# KIP_2Schematic.net
KiCad netlist of a schematic drawn in Altium Designer
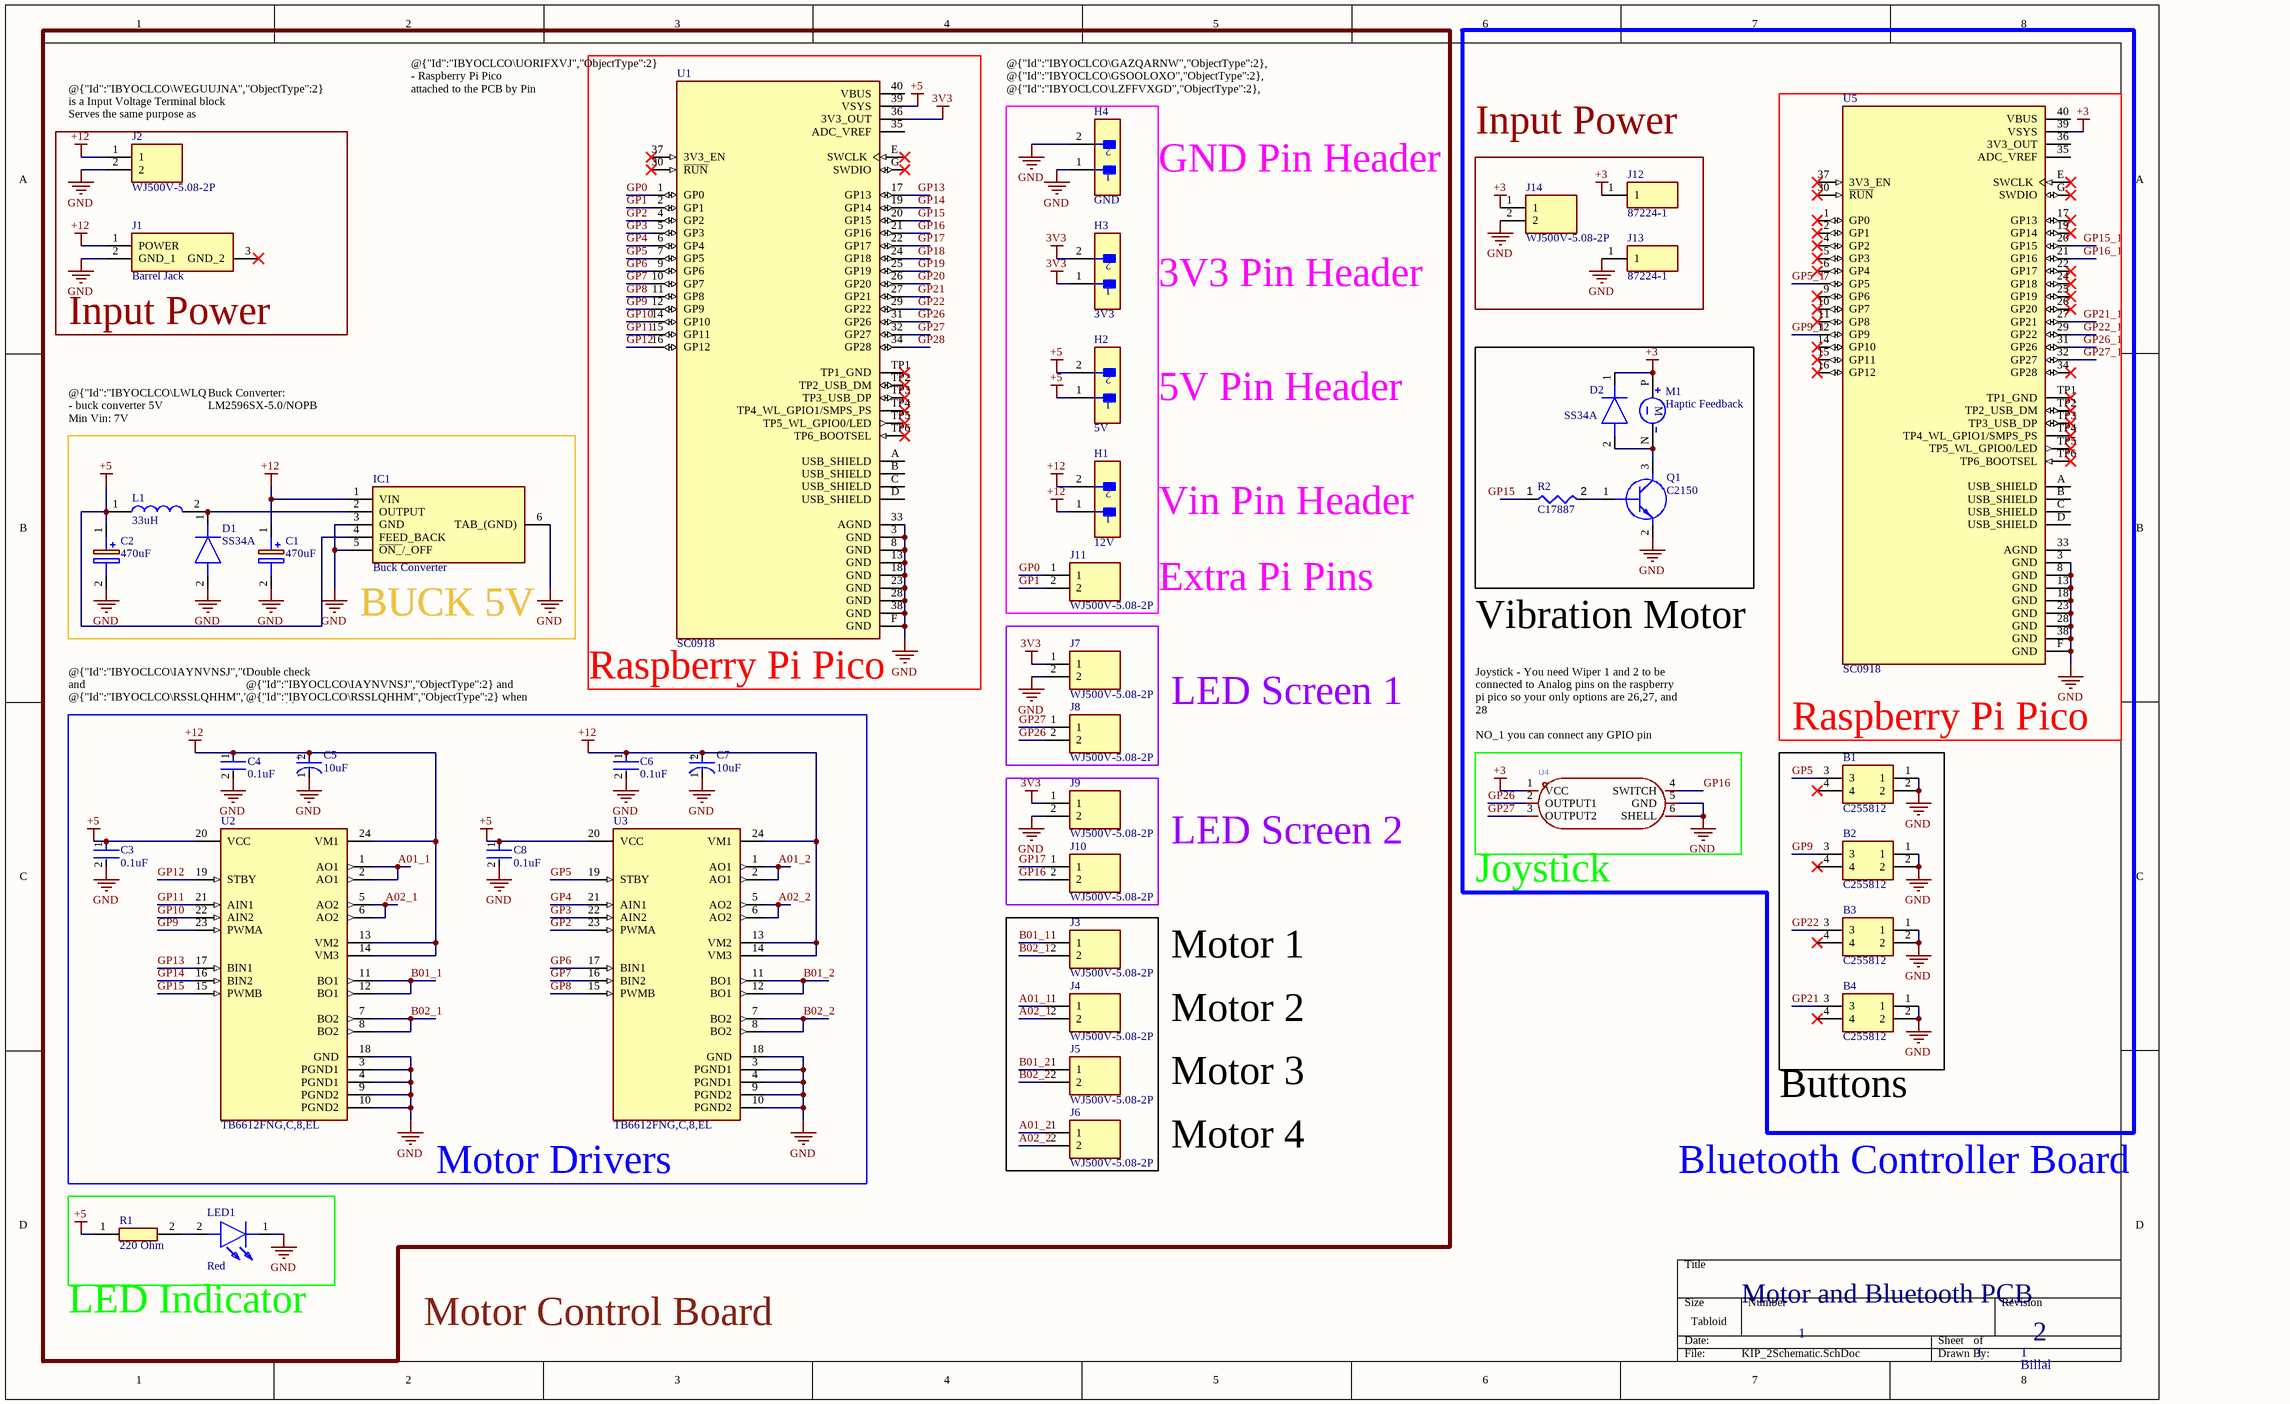
[diagram p0: KIP_2Schematic.SchDoc]

(export (version "E")
  (design (tool "Eeschema 10.0.6"))
  (components
    (comp (ref "B1")
      (value "C255812")
      (footprint "Button")
      (description "Switch")
      (fields (field (name "MANUFACTURER_PART_NUMBER") "1TS005F-2500-5001"))
      (libsource (lib "*") (part "1TS005F-2500-5001"))
    )
    (comp (ref "B2")
      (value "C255812")
      (footprint "Button")
      (description "Switch")
      (fields (field (name "MANUFACTURER_PART_NUMBER") "1TS005F-2500-5001"))
      (libsource (lib "*") (part "1TS005F-2500-5001"))
    )
    (comp (ref "B3")
      (value "C255812")
      (footprint "Button")
      (description "Switch")
      (fields (field (name "MANUFACTURER_PART_NUMBER") "1TS005F-2500-5001"))
      (libsource (lib "*") (part "1TS005F-2500-5001"))
    )
    (comp (ref "B4")
      (value "C255812")
      (footprint "Button")
      (description "Switch")
      (fields (field (name "MANUFACTURER_PART_NUMBER") "1TS005F-2500-5001"))
      (libsource (lib "*") (part "1TS005F-2500-5001"))
    )
    (comp (ref "C1")
      (value "470uF")
      (footprint "SamacSys:CAPPRD350W65D800H2200")
      (description "C178717")
      (fields
        (field (name "MANUFACTURER_PART_NUMBER") "EEU-FR1V471LB")
        (field (name "MOUSER PART NUMBER") "667-EEU-FR1V471LB")
      )
      (libsource (lib "*") (part "EEU-FR1V471LB"))
    )
    (comp (ref "C2")
      (value "470uF")
      (footprint "SamacSys:CAPPRD350W65D800H2200")
      (description "C178717")
      (fields
        (field (name "MANUFACTURER_PART_NUMBER") "EEU-FR1V471LB")
        (field (name "MOUSER PART NUMBER") "667-EEU-FR1V471LB")
      )
      (libsource (lib "*") (part "EEU-FR1V471LB"))
    )
    (comp (ref "C3")
      (value "0.1uF")
      (footprint "FP-CL779-IPC_C")
      (description "C307331")
      (libsource (lib "Altium Content Vault") (part "b4654b650e69147ec39a6b967a45e02"))
    )
    (comp (ref "C4")
      (value "0.1uF")
      (footprint "FP-CL779-IPC_C")
      (description "C307331")
      (libsource (lib "Altium Content Vault") (part "b4654b650e69147ec39a6b967a45e02"))
    )
    (comp (ref "C5")
      (value "10uF")
      (footprint "FP-TAJA-MFG")
      (description "C7171")
      (fields (field (name "VOLTAGE") "16V") (field (name "TOLERANCE") "10%"))
      (libsource (lib "Altium Content Vault") (part "203bc49f2ac43e59fd269a8c329ed05"))
    )
    (comp (ref "C6")
      (value "0.1uF")
      (footprint "FP-CL779-IPC_C")
      (description "C307331")
      (libsource (lib "Altium Content Vault") (part "b4654b650e69147ec39a6b967a45e02"))
    )
    (comp (ref "C7")
      (value "10uF")
      (footprint "FP-TAJA-MFG")
      (description "C7171")
      (fields (field (name "VOLTAGE") "16V") (field (name "TOLERANCE") "10%"))
      (libsource (lib "Altium Content Vault") (part "203bc49f2ac43e59fd269a8c329ed05"))
    )
    (comp (ref "C8")
      (value "0.1uF")
      (footprint "FP-CL779-IPC_C")
      (description "C307331")
      (libsource (lib "Altium Content Vault") (part "b4654b650e69147ec39a6b967a45e02"))
    )
    (comp (ref "D1")
      (value "SS34A")
      (footprint "SamacSys:DIOM5026X262N")
      (description "Diode")
      (libsource (lib "*") (part "SS34A"))
    )
    (comp (ref "D2")
      (value "SS34A")
      (footprint "SamacSys:DIOM5026X262N")
      (description "Diode")
      (libsource (lib "*") (part "SS34A"))
    )
    (comp (ref "H1")
      (value "12V")
      (footprint "FP-M20-9990246-MFG")
      (description "C492401")
      (fields
        (field (name "OCTOPART") "https://octopart.com/m20-9990246-harwin-2590635")
        (field (name "MANUFACTURER") "Harwin")
      )
      (libsource (lib "Altium Content Vault") (part "3bc925449376181038e59eaffc5286c"))
    )
    (comp (ref "H2")
      (value "5V")
      (footprint "FP-M20-9990246-MFG")
      (description "C492401")
      (fields
        (field (name "OCTOPART") "https://octopart.com/m20-9990246-harwin-2590635")
        (field (name "MANUFACTURER") "Harwin")
      )
      (libsource (lib "Altium Content Vault") (part "3bc925449376181038e59eaffc5286c"))
    )
    (comp (ref "H3")
      (value "3V3")
      (footprint "FP-M20-9990246-MFG")
      (description "C492401")
      (fields
        (field (name "OCTOPART") "https://octopart.com/m20-9990246-harwin-2590635")
        (field (name "MANUFACTURER") "Harwin")
      )
      (libsource (lib "Altium Content Vault") (part "3bc925449376181038e59eaffc5286c"))
    )
    (comp (ref "H4")
      (value "GND")
      (footprint "FP-M20-9990246-MFG")
      (description "C492401")
      (fields
        (field (name "OCTOPART") "https://octopart.com/m20-9990246-harwin-2590635")
        (field (name "MANUFACTURER") "Harwin")
      )
      (libsource (lib "Altium Content Vault") (part "3bc925449376181038e59eaffc5286c"))
    )
    (comp (ref "IC1")
      (value "Buck Converter")
      (footprint "SamacSys:KTT0005B")
      (description "C10002")
      (fields
        (field (name "MANUFACTURER_PART_NUMBER") "LM2596SX-5.0/NOPB")
        (field (name "MOUSER PART NUMBER") "926-LM2596SX-5.0NOPB")
      )
      (libsource (lib "*") (part "LM2596SX-5.0_NOPB"))
    )
    (comp (ref "J1")
      (value "Barrel Jack")
      (footprint "SamacSys:694106301002_1")
      (description "C5441017")
      (fields
        (field (name "MANUFACTURER_PART_NUMBER") "694106301002")
        (field (name "MOUSER PART NUMBER") "710-694106301002")
      )
      (libsource (lib "*") (part "694106301002"))
    )
    (comp (ref "J2")
      (value "WJ500V-5.08-2P")
      (footprint "SamacSys:WJ500V5082P")
      (description "C8465")
      (libsource (lib "*") (part "WJ500V-5.08-2P"))
    )
    (comp (ref "J3")
      (value "WJ500V-5.08-2P")
      (footprint "SamacSys:WJ500V5082P")
      (description "C8465")
      (libsource (lib "*") (part "WJ500V-5.08-2P"))
    )
    (comp (ref "J4")
      (value "WJ500V-5.08-2P")
      (footprint "SamacSys:WJ500V5082P")
      (description "C8465")
      (libsource (lib "*") (part "WJ500V-5.08-2P"))
    )
    (comp (ref "J5")
      (value "WJ500V-5.08-2P")
      (footprint "SamacSys:WJ500V5082P")
      (description "C8465")
      (libsource (lib "*") (part "WJ500V-5.08-2P"))
    )
    (comp (ref "J6")
      (value "WJ500V-5.08-2P")
      (footprint "SamacSys:WJ500V5082P")
      (description "C8465")
      (libsource (lib "*") (part "WJ500V-5.08-2P"))
    )
    (comp (ref "J7")
      (value "WJ500V-5.08-2P")
      (footprint "SamacSys:WJ500V5082P")
      (description "C8465")
      (libsource (lib "*") (part "WJ500V-5.08-2P"))
    )
    (comp (ref "J8")
      (value "WJ500V-5.08-2P")
      (footprint "SamacSys:WJ500V5082P")
      (description "C8465")
      (libsource (lib "*") (part "WJ500V-5.08-2P"))
    )
    (comp (ref "J9")
      (value "WJ500V-5.08-2P")
      (footprint "SamacSys:WJ500V5082P")
      (description "C8465")
      (libsource (lib "*") (part "WJ500V-5.08-2P"))
    )
    (comp (ref "J10")
      (value "WJ500V-5.08-2P")
      (footprint "SamacSys:WJ500V5082P")
      (description "C8465")
      (libsource (lib "*") (part "WJ500V-5.08-2P"))
    )
    (comp (ref "J11")
      (value "WJ500V-5.08-2P")
      (footprint "SamacSys:WJ500V5082P")
      (description "C8465")
      (libsource (lib "*") (part "WJ500V-5.08-2P"))
    )
    (comp (ref "J12")
      (value "87224-1")
      (footprint "SamacSys:HDRV1W66P0X254_1X1_213X254X1074P")
      (description "Connector")
      (fields (field (name "MOUSER PART NUMBER") "571-872241"))
      (libsource (lib "*") (part "87224-1"))
    )
    (comp (ref "J13")
      (value "87224-1")
      (footprint "SamacSys:HDRV1W66P0X254_1X1_213X254X1074P")
      (description "Connector")
      (fields (field (name "MOUSER PART NUMBER") "571-872241"))
      (libsource (lib "*") (part "87224-1"))
    )
    (comp (ref "J14")
      (value "WJ500V-5.08-2P")
      (footprint "SamacSys:WJ500V5082P")
      (description "C8465")
      (libsource (lib "*") (part "WJ500V-5.08-2P"))
    )
    (comp (ref "L1")
      (value "33uH")
      (footprint "SamacSys:INDPM144128X650N")
      (description "C364090")
      (fields (field (name "MANUFACTURER_PART_NUMBER") "SLO1365H330MTT"))
      (libsource (lib "*") (part "SLO1365H330MTT"))
    )
    (comp (ref "LED1")
      (value "Red")
      (footprint "SamacSys:LEDC1608X70N")
      (description "C2286")
      (fields (field (name "MANUFACTURER_PART_NUMBER") "KT-0603R"))
      (libsource (lib "*") (part "KT-0603R"))
    )
    (comp (ref "M1")
      (value "Haptic Feedback")
      (footprint "Haptic Feedback")
      (libsource (lib "Schlib1") (part "Haptic Feedback"))
    )
    (comp (ref "Q1")
      (value "C2150")
      (footprint "SamacSys:SOT95P240X115-3N")
      (fields
        (field (name "MANUFACTURER_PART_NUMBER") "SS8050-G")
        (field (name "MOUSER PART NUMBER") "750-SS8050-G")
      )
      (libsource (lib "*") (part "SS8050-G"))
    )
    (comp (ref "R1")
      (value "220 Ohm")
      (footprint "SamacSys:RESC2013X65N")
      (description "C17557")
      (fields
        (field (name "MANUFACTURER_PART_NUMBER") "0805W8F2200T5E")
        (field (name "MOUSER PART NUMBER") "303-0805W8F2200T5E")
      )
      (libsource (lib "*") (part "0805W8F2200T5E"))
    )
    (comp (ref "R2")
      (value "C17887")
      (footprint "Resistor 300Ohms")
      (libsource (lib "Schlib1") (part "Resistor 300Ohms"))
    )
    (comp (ref "U1")
      (value "SC0918")
      (footprint "No pin-header Pi")
      (description "Raspberry Pi Pico W RP2040")
      (fields (field (name "MANUFACTURER") "Raspberry Pi"))
      (libsource (lib "Altium Personal") (part "SC0918"))
    )
    (comp (ref "U2")
      (value "TB6612FNG,C,8,EL")
      (footprint "FP-SSOP24-P-300-0_65A-IPC_A")
      (description "C88224")
      (libsource (lib "Altium Content Vault") (part "0e8a2fe7f3780dc9c50f4d41012bdec"))
    )
    (comp (ref "U3")
      (value "TB6612FNG,C,8,EL")
      (footprint "FP-SSOP24-P-300-0_65A-IPC_A")
      (description "C88224")
      (libsource (lib "Altium Content Vault") (part "0e8a2fe7f3780dc9c50f4d41012bdec"))
    )
    (comp (ref "U4")
      (value "C42411044")
      (footprint "Correct Joystick")
      (fields
        (field (name "MANUFACTURER") "YTL(亚特联)")
        (field (name "MANUFACTURER PART") "YHE-YG16-001 SH1B166A1")
      )
      (libsource (lib "altium-import") (part "root_0_YHE-YG16-001 SH1B166A1_"))
    )
    (comp (ref "U5")
      (value "SC0918")
      (footprint "No pin-header Pi")
      (description "Raspberry Pi Pico W RP2040")
      (fields (field (name "MANUFACTURER") "Raspberry Pi"))
      (libsource (lib "Altium Personal") (part "SC0918"))
    )
  )
  (nets
    (net (code "1") (name "+3") (class "Default")
      (node (ref "D2") (pin "1") (pinfunction "K_1") (pintype "passive"))
      (node (ref "J12") (pin "1") (pinfunction "1_1") (pintype "passive"))
      (node (ref "J14") (pin "1") (pinfunction "1_1") (pintype "passive"))
      (node (ref "M1") (pin "P") (pinfunction "POS_P") (pintype "passive"))
      (node (ref "U4") (pin "1") (pinfunction "VCC_1") (pintype "passive"))
      (node (ref "U5") (pin "39") (pinfunction "VSYS_39") (pintype "power_in"))
    )
    (net (code "2") (name "+5") (class "Default")
      (node (ref "C2") (pin "1") (pinfunction "+_1") (pintype "passive"))
      (node (ref "C3") (pin "1") (pinfunction "1_1") (pintype "passive"))
      (node (ref "C8") (pin "1") (pinfunction "1_1") (pintype "passive"))
      (node (ref "H2") (pin "1") (pinfunction "1_1") (pintype "passive"))
      (node (ref "H2") (pin "2") (pinfunction "2_2") (pintype "passive"))
      (node (ref "IC1") (pin "4") (pinfunction "FEED_BACK_4") (pintype "passive"))
      (node (ref "L1") (pin "1") (pinfunction "1_1") (pintype "passive"))
      (node (ref "R1") (pin "1") (pinfunction "1_1") (pintype "passive"))
      (node (ref "U1") (pin "39") (pinfunction "VSYS_39") (pintype "power_in"))
      (node (ref "U2") (pin "20") (pinfunction "VCC_20") (pintype "power_in"))
      (node (ref "U3") (pin "20") (pinfunction "VCC_20") (pintype "power_in"))
    )
    (net (code "3") (name "+12") (class "Default")
      (node (ref "C1") (pin "1") (pinfunction "+_1") (pintype "passive"))
      (node (ref "C4") (pin "1") (pinfunction "1_1") (pintype "passive"))
      (node (ref "C5") (pin "2") (pinfunction "A_2") (pintype "passive"))
      (node (ref "C6") (pin "1") (pinfunction "1_1") (pintype "passive"))
      (node (ref "C7") (pin "2") (pinfunction "A_2") (pintype "passive"))
      (node (ref "H1") (pin "1") (pinfunction "1_1") (pintype "passive"))
      (node (ref "H1") (pin "2") (pinfunction "2_2") (pintype "passive"))
      (node (ref "IC1") (pin "1") (pinfunction "VIN_1") (pintype "passive"))
      (node (ref "J1") (pin "1") (pinfunction "POWER_1") (pintype "passive"))
      (node (ref "J2") (pin "1") (pinfunction "1_1") (pintype "passive"))
      (node (ref "U2") (pin "13") (pinfunction "VM2_13") (pintype "power_in"))
      (node (ref "U2") (pin "14") (pinfunction "VM3_14") (pintype "power_in"))
      (node (ref "U2") (pin "24") (pinfunction "VM1_24") (pintype "power_in"))
      (node (ref "U3") (pin "13") (pinfunction "VM2_13") (pintype "power_in"))
      (node (ref "U3") (pin "14") (pinfunction "VM3_14") (pintype "power_in"))
      (node (ref "U3") (pin "24") (pinfunction "VM1_24") (pintype "power_in"))
    )
    (net (code "4") (name "/A01_1") (class "Default")
      (node (ref "J4") (pin "1") (pinfunction "1_1") (pintype "passive"))
      (node (ref "U2") (pin "1") (pinfunction "AO1_1") (pintype "output"))
      (node (ref "U2") (pin "2") (pinfunction "AO1_2") (pintype "output"))
    )
    (net (code "5") (name "/A01_2") (class "Default")
      (node (ref "J6") (pin "1") (pinfunction "1_1") (pintype "passive"))
      (node (ref "U3") (pin "1") (pinfunction "AO1_1") (pintype "output"))
      (node (ref "U3") (pin "2") (pinfunction "AO1_2") (pintype "output"))
    )
    (net (code "6") (name "/A02_1") (class "Default")
      (node (ref "J4") (pin "2") (pinfunction "2_2") (pintype "passive"))
      (node (ref "U2") (pin "5") (pinfunction "AO2_5") (pintype "output"))
      (node (ref "U2") (pin "6") (pinfunction "AO2_6") (pintype "output"))
    )
    (net (code "7") (name "/A02_2") (class "Default")
      (node (ref "J6") (pin "2") (pinfunction "2_2") (pintype "passive"))
      (node (ref "U3") (pin "5") (pinfunction "AO2_5") (pintype "output"))
      (node (ref "U3") (pin "6") (pinfunction "AO2_6") (pintype "output"))
    )
    (net (code "8") (name "/B01_1") (class "Default")
      (node (ref "J3") (pin "1") (pinfunction "1_1") (pintype "passive"))
      (node (ref "U2") (pin "11") (pinfunction "BO1_11") (pintype "output"))
      (node (ref "U2") (pin "12") (pinfunction "BO1_12") (pintype "output"))
    )
    (net (code "9") (name "/B01_2") (class "Default")
      (node (ref "J5") (pin "1") (pinfunction "1_1") (pintype "passive"))
      (node (ref "U3") (pin "11") (pinfunction "BO1_11") (pintype "output"))
      (node (ref "U3") (pin "12") (pinfunction "BO1_12") (pintype "output"))
    )
    (net (code "10") (name "/B02_1") (class "Default")
      (node (ref "J3") (pin "2") (pinfunction "2_2") (pintype "passive"))
      (node (ref "U2") (pin "7") (pinfunction "BO2_7") (pintype "output"))
      (node (ref "U2") (pin "8") (pinfunction "BO2_8") (pintype "output"))
    )
    (net (code "11") (name "/B02_2") (class "Default")
      (node (ref "J5") (pin "2") (pinfunction "2_2") (pintype "passive"))
      (node (ref "U3") (pin "7") (pinfunction "BO2_7") (pintype "output"))
      (node (ref "U3") (pin "8") (pinfunction "BO2_8") (pintype "output"))
    )
    (net (code "12") (name "/GP0") (class "Default")
      (node (ref "J11") (pin "1") (pinfunction "1_1") (pintype "passive"))
      (node (ref "U1") (pin "1") (pinfunction "GP0_1") (pintype "bidirectional"))
    )
    (net (code "13") (name "/GP1") (class "Default")
      (node (ref "J11") (pin "2") (pinfunction "2_2") (pintype "passive"))
      (node (ref "U1") (pin "2") (pinfunction "GP1_2") (pintype "bidirectional"))
    )
    (net (code "14") (name "/GP2") (class "Default")
      (node (ref "U1") (pin "4") (pinfunction "GP2_4") (pintype "bidirectional"))
      (node (ref "U3") (pin "23") (pinfunction "PWMA_23") (pintype "input"))
    )
    (net (code "15") (name "/GP3") (class "Default")
      (node (ref "U1") (pin "5") (pinfunction "GP3_5") (pintype "bidirectional"))
      (node (ref "U3") (pin "22") (pinfunction "AIN2_22") (pintype "input"))
    )
    (net (code "16") (name "/GP4") (class "Default")
      (node (ref "U1") (pin "6") (pinfunction "GP4_6") (pintype "bidirectional"))
      (node (ref "U3") (pin "21") (pinfunction "AIN1_21") (pintype "input"))
    )
    (net (code "17") (name "/GP5") (class "Default")
      (node (ref "B1") (pin "3") (pinfunction "3_3") (pintype "passive"))
      (node (ref "U1") (pin "7") (pinfunction "GP5_7") (pintype "bidirectional"))
      (node (ref "U3") (pin "19") (pinfunction "STBY_19") (pintype "input"))
    )
    (net (code "18") (name "/GP5_1") (class "Default")
      (node (ref "U5") (pin "7") (pinfunction "GP5_7") (pintype "bidirectional"))
    )
    (net (code "19") (name "/GP6") (class "Default")
      (node (ref "U1") (pin "9") (pinfunction "GP6_9") (pintype "bidirectional"))
      (node (ref "U3") (pin "17") (pinfunction "BIN1_17") (pintype "input"))
    )
    (net (code "20") (name "/GP7") (class "Default")
      (node (ref "U1") (pin "10") (pinfunction "GP7_10") (pintype "bidirectional"))
      (node (ref "U3") (pin "16") (pinfunction "BIN2_16") (pintype "input"))
    )
    (net (code "21") (name "/GP8") (class "Default")
      (node (ref "U1") (pin "11") (pinfunction "GP8_11") (pintype "bidirectional"))
      (node (ref "U3") (pin "15") (pinfunction "PWMB_15") (pintype "input"))
    )
    (net (code "22") (name "/GP9") (class "Default")
      (node (ref "B2") (pin "3") (pinfunction "3_3") (pintype "passive"))
      (node (ref "U1") (pin "12") (pinfunction "GP9_12") (pintype "bidirectional"))
      (node (ref "U2") (pin "23") (pinfunction "PWMA_23") (pintype "input"))
    )
    (net (code "23") (name "/GP9_1") (class "Default")
      (node (ref "U5") (pin "12") (pinfunction "GP9_12") (pintype "bidirectional"))
    )
    (net (code "24") (name "/GP10") (class "Default")
      (node (ref "U1") (pin "14") (pinfunction "GP10_14") (pintype "bidirectional"))
      (node (ref "U2") (pin "22") (pinfunction "AIN2_22") (pintype "input"))
    )
    (net (code "25") (name "/GP11") (class "Default")
      (node (ref "U1") (pin "15") (pinfunction "GP11_15") (pintype "bidirectional"))
      (node (ref "U2") (pin "21") (pinfunction "AIN1_21") (pintype "input"))
    )
    (net (code "26") (name "/GP12") (class "Default")
      (node (ref "U1") (pin "16") (pinfunction "GP12_16") (pintype "bidirectional"))
      (node (ref "U2") (pin "19") (pinfunction "STBY_19") (pintype "input"))
    )
    (net (code "27") (name "/GP13") (class "Default")
      (node (ref "U1") (pin "17") (pinfunction "GP13_17") (pintype "bidirectional"))
      (node (ref "U2") (pin "17") (pinfunction "BIN1_17") (pintype "input"))
    )
    (net (code "28") (name "/GP14") (class "Default")
      (node (ref "U1") (pin "19") (pinfunction "GP14_19") (pintype "bidirectional"))
      (node (ref "U2") (pin "16") (pinfunction "BIN2_16") (pintype "input"))
    )
    (net (code "29") (name "/GP15") (class "Default")
      (node (ref "U1") (pin "20") (pinfunction "GP15_20") (pintype "bidirectional"))
      (node (ref "U2") (pin "15") (pinfunction "PWMB_15") (pintype "input"))
    )
    (net (code "30") (name "/GP15_1") (class "Default")
      (node (ref "U5") (pin "20") (pinfunction "GP15_20") (pintype "bidirectional"))
    )
    (net (code "31") (name "/GP16") (class "Default")
      (node (ref "J10") (pin "2") (pinfunction "2_2") (pintype "passive"))
      (node (ref "U1") (pin "21") (pinfunction "GP16_21") (pintype "bidirectional"))
      (node (ref "U4") (pin "4") (pinfunction "SWITCH_4") (pintype "passive"))
    )
    (net (code "32") (name "/GP16_1") (class "Default")
      (node (ref "U5") (pin "21") (pinfunction "GP16_21") (pintype "bidirectional"))
    )
    (net (code "33") (name "/GP17") (class "Default")
      (node (ref "J10") (pin "1") (pinfunction "1_1") (pintype "passive"))
      (node (ref "U1") (pin "22") (pinfunction "GP17_22") (pintype "bidirectional"))
    )
    (net (code "34") (name "/GP18") (class "Default")
      (node (ref "U1") (pin "24") (pinfunction "GP18_24") (pintype "bidirectional"))
    )
    (net (code "35") (name "/GP19") (class "Default")
      (node (ref "U1") (pin "25") (pinfunction "GP19_25") (pintype "bidirectional"))
    )
    (net (code "36") (name "/GP20") (class "Default")
      (node (ref "U1") (pin "26") (pinfunction "GP20_26") (pintype "bidirectional"))
    )
    (net (code "37") (name "/GP21") (class "Default")
      (node (ref "B4") (pin "3") (pinfunction "3_3") (pintype "passive"))
      (node (ref "U1") (pin "27") (pinfunction "GP21_27") (pintype "bidirectional"))
    )
    (net (code "38") (name "/GP21_1") (class "Default")
      (node (ref "U5") (pin "27") (pinfunction "GP21_27") (pintype "bidirectional"))
    )
    (net (code "39") (name "/GP22") (class "Default")
      (node (ref "B3") (pin "3") (pinfunction "3_3") (pintype "passive"))
      (node (ref "U1") (pin "29") (pinfunction "GP22_29") (pintype "bidirectional"))
    )
    (net (code "40") (name "/GP22_1") (class "Default")
      (node (ref "U5") (pin "29") (pinfunction "GP22_29") (pintype "bidirectional"))
    )
    (net (code "41") (name "/GP26") (class "Default")
      (node (ref "J8") (pin "2") (pinfunction "2_2") (pintype "passive"))
      (node (ref "U1") (pin "31") (pinfunction "GP26_31") (pintype "bidirectional"))
      (node (ref "U4") (pin "2") (pinfunction "OUTPUT1_2") (pintype "passive"))
    )
    (net (code "42") (name "/GP26_1") (class "Default")
      (node (ref "U5") (pin "31") (pinfunction "GP26_31") (pintype "bidirectional"))
    )
    (net (code "43") (name "/GP27") (class "Default")
      (node (ref "J8") (pin "1") (pinfunction "1_1") (pintype "passive"))
      (node (ref "U1") (pin "32") (pinfunction "GP27_32") (pintype "bidirectional"))
      (node (ref "U4") (pin "3") (pinfunction "OUTPUT2_3") (pintype "passive"))
    )
    (net (code "44") (name "/GP27_1") (class "Default")
      (node (ref "U5") (pin "32") (pinfunction "GP27_32") (pintype "bidirectional"))
    )
    (net (code "45") (name "/GP28") (class "Default")
      (node (ref "U1") (pin "34") (pinfunction "GP28_34") (pintype "bidirectional"))
    )
    (net (code "46") (name "3V3") (class "Default")
      (node (ref "H3") (pin "1") (pinfunction "1_1") (pintype "passive"))
      (node (ref "H3") (pin "2") (pinfunction "2_2") (pintype "passive"))
      (node (ref "J7") (pin "1") (pinfunction "1_1") (pintype "passive"))
      (node (ref "J9") (pin "1") (pinfunction "1_1") (pintype "passive"))
      (node (ref "U1") (pin "36") (pinfunction "3V3_OUT_36") (pintype "power_in"))
    )
    (net (code "47") (name "GND") (class "Default")
      (node (ref "B1") (pin "1") (pinfunction "1_1") (pintype "passive"))
      (node (ref "B1") (pin "2") (pinfunction "2_2") (pintype "passive"))
      (node (ref "B2") (pin "1") (pinfunction "1_1") (pintype "passive"))
      (node (ref "B2") (pin "2") (pinfunction "2_2") (pintype "passive"))
      (node (ref "B3") (pin "1") (pinfunction "1_1") (pintype "passive"))
      (node (ref "B3") (pin "2") (pinfunction "2_2") (pintype "passive"))
      (node (ref "B4") (pin "1") (pinfunction "1_1") (pintype "passive"))
      (node (ref "B4") (pin "2") (pinfunction "2_2") (pintype "passive"))
      (node (ref "C1") (pin "2") (pinfunction "-_2") (pintype "passive"))
      (node (ref "C2") (pin "2") (pinfunction "-_2") (pintype "passive"))
      (node (ref "C3") (pin "2") (pinfunction "2_2") (pintype "passive"))
      (node (ref "C4") (pin "2") (pinfunction "2_2") (pintype "passive"))
      (node (ref "C5") (pin "1") (pinfunction "C_1") (pintype "passive"))
      (node (ref "C6") (pin "2") (pinfunction "2_2") (pintype "passive"))
      (node (ref "C7") (pin "1") (pinfunction "C_1") (pintype "passive"))
      (node (ref "C8") (pin "2") (pinfunction "2_2") (pintype "passive"))
      (node (ref "D1") (pin "2") (pinfunction "A_2") (pintype "passive"))
      (node (ref "H4") (pin "1") (pinfunction "1_1") (pintype "passive"))
      (node (ref "H4") (pin "2") (pinfunction "2_2") (pintype "passive"))
      (node (ref "IC1") (pin "3") (pinfunction "GND_3") (pintype "passive"))
      (node (ref "IC1") (pin "5") (pinfunction "~{ON_}/_OFF_5") (pintype "passive"))
      (node (ref "IC1") (pin "6") (pinfunction "TAB_(GND)_6") (pintype "passive"))
      (node (ref "J1") (pin "2") (pinfunction "GND_1_2") (pintype "passive"))
      (node (ref "J13") (pin "1") (pinfunction "1_1") (pintype "passive"))
      (node (ref "J14") (pin "2") (pinfunction "2_2") (pintype "passive"))
      (node (ref "J2") (pin "2") (pinfunction "2_2") (pintype "passive"))
      (node (ref "J7") (pin "2") (pinfunction "2_2") (pintype "passive"))
      (node (ref "J9") (pin "2") (pinfunction "2_2") (pintype "passive"))
      (node (ref "LED1") (pin "1") (pinfunction "K_1") (pintype "passive"))
      (node (ref "Q1") (pin "2") (pinfunction "E_2") (pintype "passive"))
      (node (ref "U1") (pin "13") (pinfunction "GND_13") (pintype "power_in"))
      (node (ref "U1") (pin "18") (pinfunction "GND_18") (pintype "power_in"))
      (node (ref "U1") (pin "23") (pinfunction "GND_23") (pintype "power_in"))
      (node (ref "U1") (pin "28") (pinfunction "GND_28") (pintype "power_in"))
      (node (ref "U1") (pin "3") (pinfunction "GND_3") (pintype "power_in"))
      (node (ref "U1") (pin "33") (pinfunction "AGND_33") (pintype "power_in"))
      (node (ref "U1") (pin "38") (pinfunction "GND_38") (pintype "power_in"))
      (node (ref "U1") (pin "8") (pinfunction "GND_8") (pintype "power_in"))
      (node (ref "U1") (pin "F") (pinfunction "GND_F") (pintype "power_in"))
      (node (ref "U2") (pin "10") (pinfunction "PGND2_10") (pintype "power_in"))
      (node (ref "U2") (pin "18") (pinfunction "GND_18") (pintype "power_in"))
      (node (ref "U2") (pin "3") (pinfunction "PGND1_3") (pintype "power_in"))
      (node (ref "U2") (pin "4") (pinfunction "PGND1_4") (pintype "power_in"))
      (node (ref "U2") (pin "9") (pinfunction "PGND2_9") (pintype "power_in"))
      (node (ref "U3") (pin "10") (pinfunction "PGND2_10") (pintype "power_in"))
      (node (ref "U3") (pin "18") (pinfunction "GND_18") (pintype "power_in"))
      (node (ref "U3") (pin "3") (pinfunction "PGND1_3") (pintype "power_in"))
      (node (ref "U3") (pin "4") (pinfunction "PGND1_4") (pintype "power_in"))
      (node (ref "U3") (pin "9") (pinfunction "PGND2_9") (pintype "power_in"))
      (node (ref "U4") (pin "5") (pinfunction "GND_5") (pintype "passive"))
      (node (ref "U4") (pin "6") (pinfunction "SHELL_6") (pintype "passive"))
      (node (ref "U5") (pin "13") (pinfunction "GND_13") (pintype "power_in"))
      (node (ref "U5") (pin "18") (pinfunction "GND_18") (pintype "power_in"))
      (node (ref "U5") (pin "23") (pinfunction "GND_23") (pintype "power_in"))
      (node (ref "U5") (pin "28") (pinfunction "GND_28") (pintype "power_in"))
      (node (ref "U5") (pin "3") (pinfunction "GND_3") (pintype "power_in"))
      (node (ref "U5") (pin "38") (pinfunction "GND_38") (pintype "power_in"))
      (node (ref "U5") (pin "8") (pinfunction "GND_8") (pintype "power_in"))
      (node (ref "U5") (pin "F") (pinfunction "GND_F") (pintype "power_in"))
    )
    (net (code "48") (name "Net-(D1-K)") (class "Default")
      (node (ref "D1") (pin "1") (pinfunction "K_1") (pintype "passive"))
      (node (ref "IC1") (pin "2") (pinfunction "OUTPUT_2") (pintype "passive"))
      (node (ref "L1") (pin "2") (pinfunction "2_2") (pintype "passive"))
    )
    (net (code "49") (name "Net-(D2-A)") (class "Default")
      (node (ref "D2") (pin "2") (pinfunction "A_2") (pintype "passive"))
      (node (ref "M1") (pin "N") (pinfunction "NEG_N") (pintype "passive"))
      (node (ref "Q1") (pin "3") (pinfunction "C_3") (pintype "passive"))
    )
    (net (code "50") (name "Net-(LED1-A)") (class "Default")
      (node (ref "LED1") (pin "2") (pinfunction "A_2") (pintype "passive"))
      (node (ref "R1") (pin "2") (pinfunction "2_2") (pintype "passive"))
    )
    (net (code "51") (name "Net-(Q1-B)") (class "Default")
      (node (ref "Q1") (pin "1") (pinfunction "B_1") (pintype "passive"))
      (node (ref "R2") (pin "2") (pinfunction "2_2") (pintype "passive"))
    )
    (net (code "52") (name "unconnected-(B1-Pad4)") (class "Default")
      (node (ref "B1") (pin "4") (pinfunction "4_4") (pintype "passive+no_connect"))
    )
    (net (code "53") (name "unconnected-(B2-Pad4)") (class "Default")
      (node (ref "B2") (pin "4") (pinfunction "4_4") (pintype "passive+no_connect"))
    )
    (net (code "54") (name "unconnected-(B3-Pad4)") (class "Default")
      (node (ref "B3") (pin "4") (pinfunction "4_4") (pintype "passive+no_connect"))
    )
    (net (code "55") (name "unconnected-(B4-Pad4)") (class "Default")
      (node (ref "B4") (pin "4") (pinfunction "4_4") (pintype "passive+no_connect"))
    )
    (net (code "56") (name "unconnected-(J1-GND_2-Pad3)") (class "Default")
      (node (ref "J1") (pin "3") (pinfunction "GND_2_3") (pintype "passive+no_connect"))
    )
    (net (code "57") (name "unconnected-(R2-Pad1)") (class "Default")
      (node (ref "R2") (pin "1") (pinfunction "1_1") (pintype "passive"))
    )
    (net (code "58") (name "unconnected-(U1-3V3_EN-Pad37)") (class "Default")
      (node (ref "U1") (pin "37") (pinfunction "3V3_EN_37") (pintype "input+no_connect"))
    )
    (net (code "59") (name "unconnected-(U1-ADC_VREF-Pad35)") (class "Default")
      (node (ref "U1") (pin "35") (pinfunction "ADC_VREF_35") (pintype "power_in"))
    )
    (net (code "60") (name "unconnected-(U1-SWCLK-PadE)") (class "Default")
      (node (ref "U1") (pin "E") (pinfunction "SWCLK_E") (pintype "input+no_connect"))
    )
    (net (code "61") (name "unconnected-(U1-SWDIO-PadG)") (class "Default")
      (node (ref "U1") (pin "G") (pinfunction "SWDIO_G") (pintype "bidirectional+no_connect"))
    )
    (net (code "62") (name "unconnected-(U1-TP1_GND-PadTP1)") (class "Default")
      (node (ref "U1") (pin "TP1") (pinfunction "TP1_GND_TP1") (pintype "power_in+no_connect"))
    )
    (net (code "63") (name "unconnected-(U1-TP2_USB_DM-PadTP2)") (class "Default")
      (node (ref "U1") (pin "TP2") (pinfunction "TP2_USB_DM_TP2") (pintype "bidirectional+no_connect"))
    )
    (net (code "64") (name "unconnected-(U1-TP3_USB_DP-PadTP3)") (class "Default")
      (node (ref "U1") (pin "TP3") (pinfunction "TP3_USB_DP_TP3") (pintype "bidirectional+no_connect"))
    )
    (net (code "65") (name "unconnected-(U1-TP4_WL_GPIO1{slash}SMPS_PS-PadTP4)") (class "Default")
      (node (ref "U1") (pin "TP4") (pinfunction "TP4_WL_GPIO1/SMPS_PS_TP4") (pintype "passive+no_connect"))
    )
    (net (code "66") (name "unconnected-(U1-TP5_WL_GPIO0{slash}LED-PadTP5)") (class "Default")
      (node (ref "U1") (pin "TP5") (pinfunction "TP5_WL_GPIO0/LED_TP5") (pintype "output+no_connect"))
    )
    (net (code "67") (name "unconnected-(U1-TP6_BOOTSEL-PadTP6)") (class "Default")
      (node (ref "U1") (pin "TP6") (pinfunction "TP6_BOOTSEL_TP6") (pintype "input+no_connect"))
    )
    (net (code "68") (name "unconnected-(U1-USB_SHIELD-PadA)") (class "Default")
      (node (ref "U1") (pin "A") (pinfunction "USB_SHIELD_A") (pintype "power_in"))
    )
    (net (code "69") (name "unconnected-(U1-USB_SHIELD-PadB)") (class "Default")
      (node (ref "U1") (pin "B") (pinfunction "USB_SHIELD_B") (pintype "power_in"))
    )
    (net (code "70") (name "unconnected-(U1-USB_SHIELD-PadC)") (class "Default")
      (node (ref "U1") (pin "C") (pinfunction "USB_SHIELD_C") (pintype "power_in"))
    )
    (net (code "71") (name "unconnected-(U1-USB_SHIELD-PadD)") (class "Default")
      (node (ref "U1") (pin "D") (pinfunction "USB_SHIELD_D") (pintype "power_in"))
    )
    (net (code "72") (name "unconnected-(U1-VBUS-Pad40)") (class "Default")
      (node (ref "U1") (pin "40") (pinfunction "VBUS_40") (pintype "power_in"))
    )
    (net (code "73") (name "unconnected-(U1-~{RUN}-Pad30)") (class "Default")
      (node (ref "U1") (pin "30") (pinfunction "~{RUN}_30") (pintype "input+no_connect"))
    )
    (net (code "74") (name "unconnected-(U5-3V3_EN-Pad37)") (class "Default")
      (node (ref "U5") (pin "37") (pinfunction "3V3_EN_37") (pintype "input+no_connect"))
    )
    (net (code "75") (name "unconnected-(U5-3V3_OUT-Pad36)") (class "Default")
      (node (ref "U5") (pin "36") (pinfunction "3V3_OUT_36") (pintype "power_in"))
    )
    (net (code "76") (name "unconnected-(U5-ADC_VREF-Pad35)") (class "Default")
      (node (ref "U5") (pin "35") (pinfunction "ADC_VREF_35") (pintype "power_in"))
    )
    (net (code "77") (name "unconnected-(U5-AGND-Pad33)") (class "Default")
      (node (ref "U5") (pin "33") (pinfunction "AGND_33") (pintype "power_in"))
    )
    (net (code "78") (name "unconnected-(U5-GP0-Pad1)") (class "Default")
      (node (ref "U5") (pin "1") (pinfunction "GP0_1") (pintype "bidirectional+no_connect"))
    )
    (net (code "79") (name "unconnected-(U5-GP1-Pad2)") (class "Default")
      (node (ref "U5") (pin "2") (pinfunction "GP1_2") (pintype "bidirectional+no_connect"))
    )
    (net (code "80") (name "unconnected-(U5-GP2-Pad4)") (class "Default")
      (node (ref "U5") (pin "4") (pinfunction "GP2_4") (pintype "bidirectional+no_connect"))
    )
    (net (code "81") (name "unconnected-(U5-GP3-Pad5)") (class "Default")
      (node (ref "U5") (pin "5") (pinfunction "GP3_5") (pintype "bidirectional+no_connect"))
    )
    (net (code "82") (name "unconnected-(U5-GP4-Pad6)") (class "Default")
      (node (ref "U5") (pin "6") (pinfunction "GP4_6") (pintype "bidirectional+no_connect"))
    )
    (net (code "83") (name "unconnected-(U5-GP6-Pad9)") (class "Default")
      (node (ref "U5") (pin "9") (pinfunction "GP6_9") (pintype "bidirectional+no_connect"))
    )
    (net (code "84") (name "unconnected-(U5-GP7-Pad10)") (class "Default")
      (node (ref "U5") (pin "10") (pinfunction "GP7_10") (pintype "bidirectional+no_connect"))
    )
    (net (code "85") (name "unconnected-(U5-GP8-Pad11)") (class "Default")
      (node (ref "U5") (pin "11") (pinfunction "GP8_11") (pintype "bidirectional+no_connect"))
    )
    (net (code "86") (name "unconnected-(U5-GP10-Pad14)") (class "Default")
      (node (ref "U5") (pin "14") (pinfunction "GP10_14") (pintype "bidirectional+no_connect"))
    )
    (net (code "87") (name "unconnected-(U5-GP11-Pad15)") (class "Default")
      (node (ref "U5") (pin "15") (pinfunction "GP11_15") (pintype "bidirectional+no_connect"))
    )
    (net (code "88") (name "unconnected-(U5-GP12-Pad16)") (class "Default")
      (node (ref "U5") (pin "16") (pinfunction "GP12_16") (pintype "bidirectional+no_connect"))
    )
    (net (code "89") (name "unconnected-(U5-GP13-Pad17)") (class "Default")
      (node (ref "U5") (pin "17") (pinfunction "GP13_17") (pintype "bidirectional+no_connect"))
    )
    (net (code "90") (name "unconnected-(U5-GP14-Pad19)") (class "Default")
      (node (ref "U5") (pin "19") (pinfunction "GP14_19") (pintype "bidirectional+no_connect"))
    )
    (net (code "91") (name "unconnected-(U5-GP17-Pad22)") (class "Default")
      (node (ref "U5") (pin "22") (pinfunction "GP17_22") (pintype "bidirectional+no_connect"))
    )
    (net (code "92") (name "unconnected-(U5-GP18-Pad24)") (class "Default")
      (node (ref "U5") (pin "24") (pinfunction "GP18_24") (pintype "bidirectional+no_connect"))
    )
    (net (code "93") (name "unconnected-(U5-GP19-Pad25)") (class "Default")
      (node (ref "U5") (pin "25") (pinfunction "GP19_25") (pintype "bidirectional+no_connect"))
    )
    (net (code "94") (name "unconnected-(U5-GP20-Pad26)") (class "Default")
      (node (ref "U5") (pin "26") (pinfunction "GP20_26") (pintype "bidirectional+no_connect"))
    )
    (net (code "95") (name "unconnected-(U5-GP28-Pad34)") (class "Default")
      (node (ref "U5") (pin "34") (pinfunction "GP28_34") (pintype "bidirectional+no_connect"))
    )
    (net (code "96") (name "unconnected-(U5-SWCLK-PadE)") (class "Default")
      (node (ref "U5") (pin "E") (pinfunction "SWCLK_E") (pintype "input+no_connect"))
    )
    (net (code "97") (name "unconnected-(U5-SWDIO-PadG)") (class "Default")
      (node (ref "U5") (pin "G") (pinfunction "SWDIO_G") (pintype "bidirectional+no_connect"))
    )
    (net (code "98") (name "unconnected-(U5-TP1_GND-PadTP1)") (class "Default")
      (node (ref "U5") (pin "TP1") (pinfunction "TP1_GND_TP1") (pintype "power_in+no_connect"))
    )
    (net (code "99") (name "unconnected-(U5-TP2_USB_DM-PadTP2)") (class "Default")
      (node (ref "U5") (pin "TP2") (pinfunction "TP2_USB_DM_TP2") (pintype "bidirectional+no_connect"))
    )
    (net (code "100") (name "unconnected-(U5-TP3_USB_DP-PadTP3)") (class "Default")
      (node (ref "U5") (pin "TP3") (pinfunction "TP3_USB_DP_TP3") (pintype "bidirectional+no_connect"))
    )
    (net (code "101") (name "unconnected-(U5-TP4_WL_GPIO1{slash}SMPS_PS-PadTP4)") (class "Default")
      (node (ref "U5") (pin "TP4") (pinfunction "TP4_WL_GPIO1/SMPS_PS_TP4") (pintype "passive+no_connect"))
    )
    (net (code "102") (name "unconnected-(U5-TP5_WL_GPIO0{slash}LED-PadTP5)") (class "Default")
      (node (ref "U5") (pin "TP5") (pinfunction "TP5_WL_GPIO0/LED_TP5") (pintype "output+no_connect"))
    )
    (net (code "103") (name "unconnected-(U5-TP6_BOOTSEL-PadTP6)") (class "Default")
      (node (ref "U5") (pin "TP6") (pinfunction "TP6_BOOTSEL_TP6") (pintype "input+no_connect"))
    )
    (net (code "104") (name "unconnected-(U5-USB_SHIELD-PadA)") (class "Default")
      (node (ref "U5") (pin "A") (pinfunction "USB_SHIELD_A") (pintype "power_in"))
    )
    (net (code "105") (name "unconnected-(U5-USB_SHIELD-PadB)") (class "Default")
      (node (ref "U5") (pin "B") (pinfunction "USB_SHIELD_B") (pintype "power_in"))
    )
    (net (code "106") (name "unconnected-(U5-USB_SHIELD-PadC)") (class "Default")
      (node (ref "U5") (pin "C") (pinfunction "USB_SHIELD_C") (pintype "power_in"))
    )
    (net (code "107") (name "unconnected-(U5-USB_SHIELD-PadD)") (class "Default")
      (node (ref "U5") (pin "D") (pinfunction "USB_SHIELD_D") (pintype "power_in"))
    )
    (net (code "108") (name "unconnected-(U5-VBUS-Pad40)") (class "Default")
      (node (ref "U5") (pin "40") (pinfunction "VBUS_40") (pintype "power_in"))
    )
    (net (code "109") (name "unconnected-(U5-~{RUN}-Pad30)") (class "Default")
      (node (ref "U5") (pin "30") (pinfunction "~{RUN}_30") (pintype "input+no_connect"))
    )
  )
)
